# AS5048_Encoder.net
KiCad netlist of a schematic drawn in EAGLE
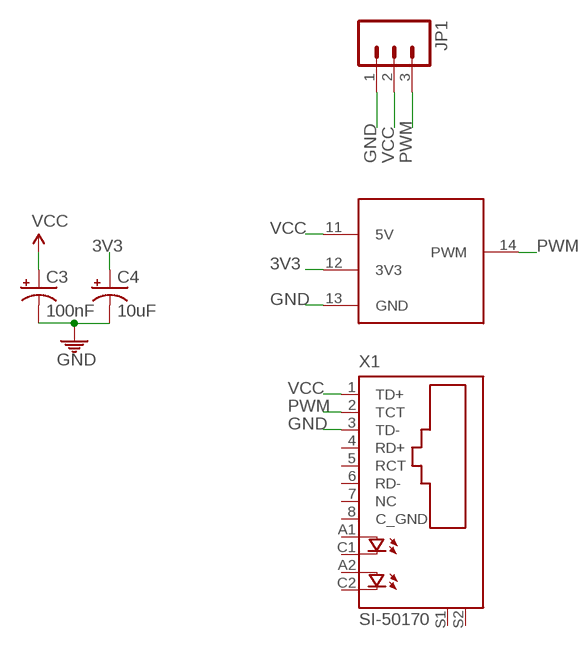
[diagram p0: schematic, sheet 1]

(export (version "E")
  (design (tool "Eeschema 10.0.6"))
  (components
    (comp (ref "C3")
      (value "100nF")
      (footprint "eagle-import:EIA3216-KIT")
      (libsource (lib "eagle-import") (part "CAP_POL1206-KIT"))
    )
    (comp (ref "C4")
      (value "10uF")
      (footprint "eagle-import:EIA3216-KIT")
      (libsource (lib "eagle-import") (part "CAP_POL1206-KIT"))
    )
    (comp (ref "JP1")
      (value "M03LOCK")
      (footprint "eagle-import:1X03_LOCK")
      (libsource (lib "eagle-import") (part "M03LOCK"))
    )
    (comp (ref "U$1")
      (value "AS5048")
      (footprint "eagle-import:TSOP14")
      (libsource (lib "eagle-import") (part "AS5048"))
    )
    (comp (ref "X1")
      (value "SI-50170")
      (footprint "eagle-import:SI-50170")
      (libsource (lib "eagle-import") (part "SI-50170"))
    )
  )
  (nets
    (net (code "1") (name "/3V3") (class "Default")
      (node (ref "C4") (pin "A") (pinfunction "+_A") (pintype "passive"))
      (node (ref "U$1") (pin "12") (pinfunction "3V3_12") (pintype "bidirectional"))
    )
    (net (code "2") (name "/PWM") (class "Default")
      (node (ref "JP1") (pin "3") (pinfunction "3_3") (pintype "passive"))
      (node (ref "U$1") (pin "14") (pinfunction "PWM_14") (pintype "bidirectional"))
      (node (ref "X1") (pin "2") (pinfunction "TCT_2") (pintype "passive"))
    )
    (net (code "3") (name "GND") (class "Default")
      (node (ref "C3") (pin "C") (pinfunction "-_C") (pintype "passive"))
      (node (ref "C4") (pin "C") (pinfunction "-_C") (pintype "passive"))
      (node (ref "JP1") (pin "1") (pinfunction "1_1") (pintype "passive"))
      (node (ref "U$1") (pin "13") (pinfunction "GND_13") (pintype "bidirectional"))
      (node (ref "X1") (pin "3") (pinfunction "TD-_3") (pintype "passive"))
    )
    (net (code "4") (name "VCC") (class "Default")
      (node (ref "C3") (pin "A") (pinfunction "+_A") (pintype "passive"))
      (node (ref "JP1") (pin "2") (pinfunction "2_2") (pintype "passive"))
      (node (ref "U$1") (pin "11") (pinfunction "5V_11") (pintype "bidirectional"))
      (node (ref "X1") (pin "1") (pinfunction "TD+_1") (pintype "passive"))
    )
    (net (code "5") (name "unconnected-(X1-A-PadA1)") (class "Default")
      (node (ref "X1") (pin "A1") (pinfunction "A_A1") (pintype "passive"))
    )
    (net (code "6") (name "unconnected-(X1-A1-PadA2)") (class "Default")
      (node (ref "X1") (pin "A2") (pinfunction "A1_A2") (pintype "passive"))
    )
    (net (code "7") (name "unconnected-(X1-C-PadC1)") (class "Default")
      (node (ref "X1") (pin "C1") (pinfunction "C_C1") (pintype "passive"))
    )
    (net (code "8") (name "unconnected-(X1-C1-PadC2)") (class "Default")
      (node (ref "X1") (pin "C2") (pinfunction "C1_C2") (pintype "passive"))
    )
    (net (code "9") (name "unconnected-(X1-C_GND-Pad8)") (class "Default")
      (node (ref "X1") (pin "8") (pinfunction "C_GND_8") (pintype "passive"))
    )
    (net (code "10") (name "unconnected-(X1-NC-Pad7)") (class "Default")
      (node (ref "X1") (pin "7") (pinfunction "NC_7") (pintype "passive"))
    )
    (net (code "11") (name "unconnected-(X1-PadS1)") (class "Default")
      (node (ref "X1") (pin "S1") (pinfunction "S1_S1") (pintype "passive"))
    )
    (net (code "12") (name "unconnected-(X1-PadS2)") (class "Default")
      (node (ref "X1") (pin "S2") (pinfunction "S2_S2") (pintype "passive"))
    )
    (net (code "13") (name "unconnected-(X1-RCT-Pad5)") (class "Default")
      (node (ref "X1") (pin "5") (pinfunction "RCT_5") (pintype "passive"))
    )
    (net (code "14") (name "unconnected-(X1-RD+-Pad4)") (class "Default")
      (node (ref "X1") (pin "4") (pinfunction "RD+_4") (pintype "passive"))
    )
    (net (code "15") (name "unconnected-(X1-RD--Pad6)") (class "Default")
      (node (ref "X1") (pin "6") (pinfunction "RD-_6") (pintype "passive"))
    )
  )
)
